# Main_Power_Switch.net
KiCad netlist of a schematic drawn in Altium Designer
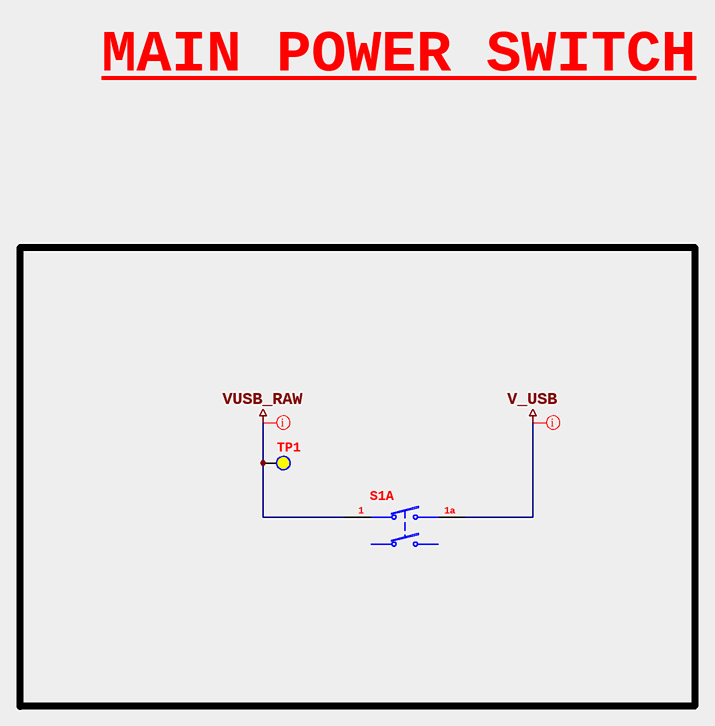
[diagram p0: Main Power Switch.SchDoc]

(export (version "E")
  (design (tool "Eeschema 10.0.6"))
  (components
    (comp (ref "S1")
      (value "R1973BBLKBLKGR0")
      (footprint "SW_ROCKER-DPST_R1973BBLKBLKGR0")
      (description "Rocker Switch DPST 9A (AC) 125 V Panel Mount, Snap-In, Right Angle")
      (fields (field (name "MANUFACTURER") "E-Switch"))
      (libsource (lib "Cellar Watchdog") (part "SW4-ON-OFF-DPST_R1973BBLKBLKGR0_TH"))
    )
    (comp (ref "TP1")
      (value "VUSB_RAW")
      (footprint "TEST POINT HOLE")
      (description "PCB Test Point")
      (libsource (lib "Cellar Watchdog") (part "Test Point"))
    )
  )
  (nets
    (net (code "1") (name "VUSB_RAW") (class "Default")
      (node (ref "S1") (pin "1") (pinfunction "1_1") (pintype "power_in"))
      (node (ref "TP1") (pin "TP") (pinfunction "TP_TP") (pintype "passive"))
    )
    (net (code "2") (name "V_USB") (class "Default")
      (node (ref "S1") (pin "1a") (pinfunction "1a_1a") (pintype "power_in"))
    )
  )
)
